# Triangular_Ear_Bass_21.net
KiCad netlist of a schematic drawn in EAGLE
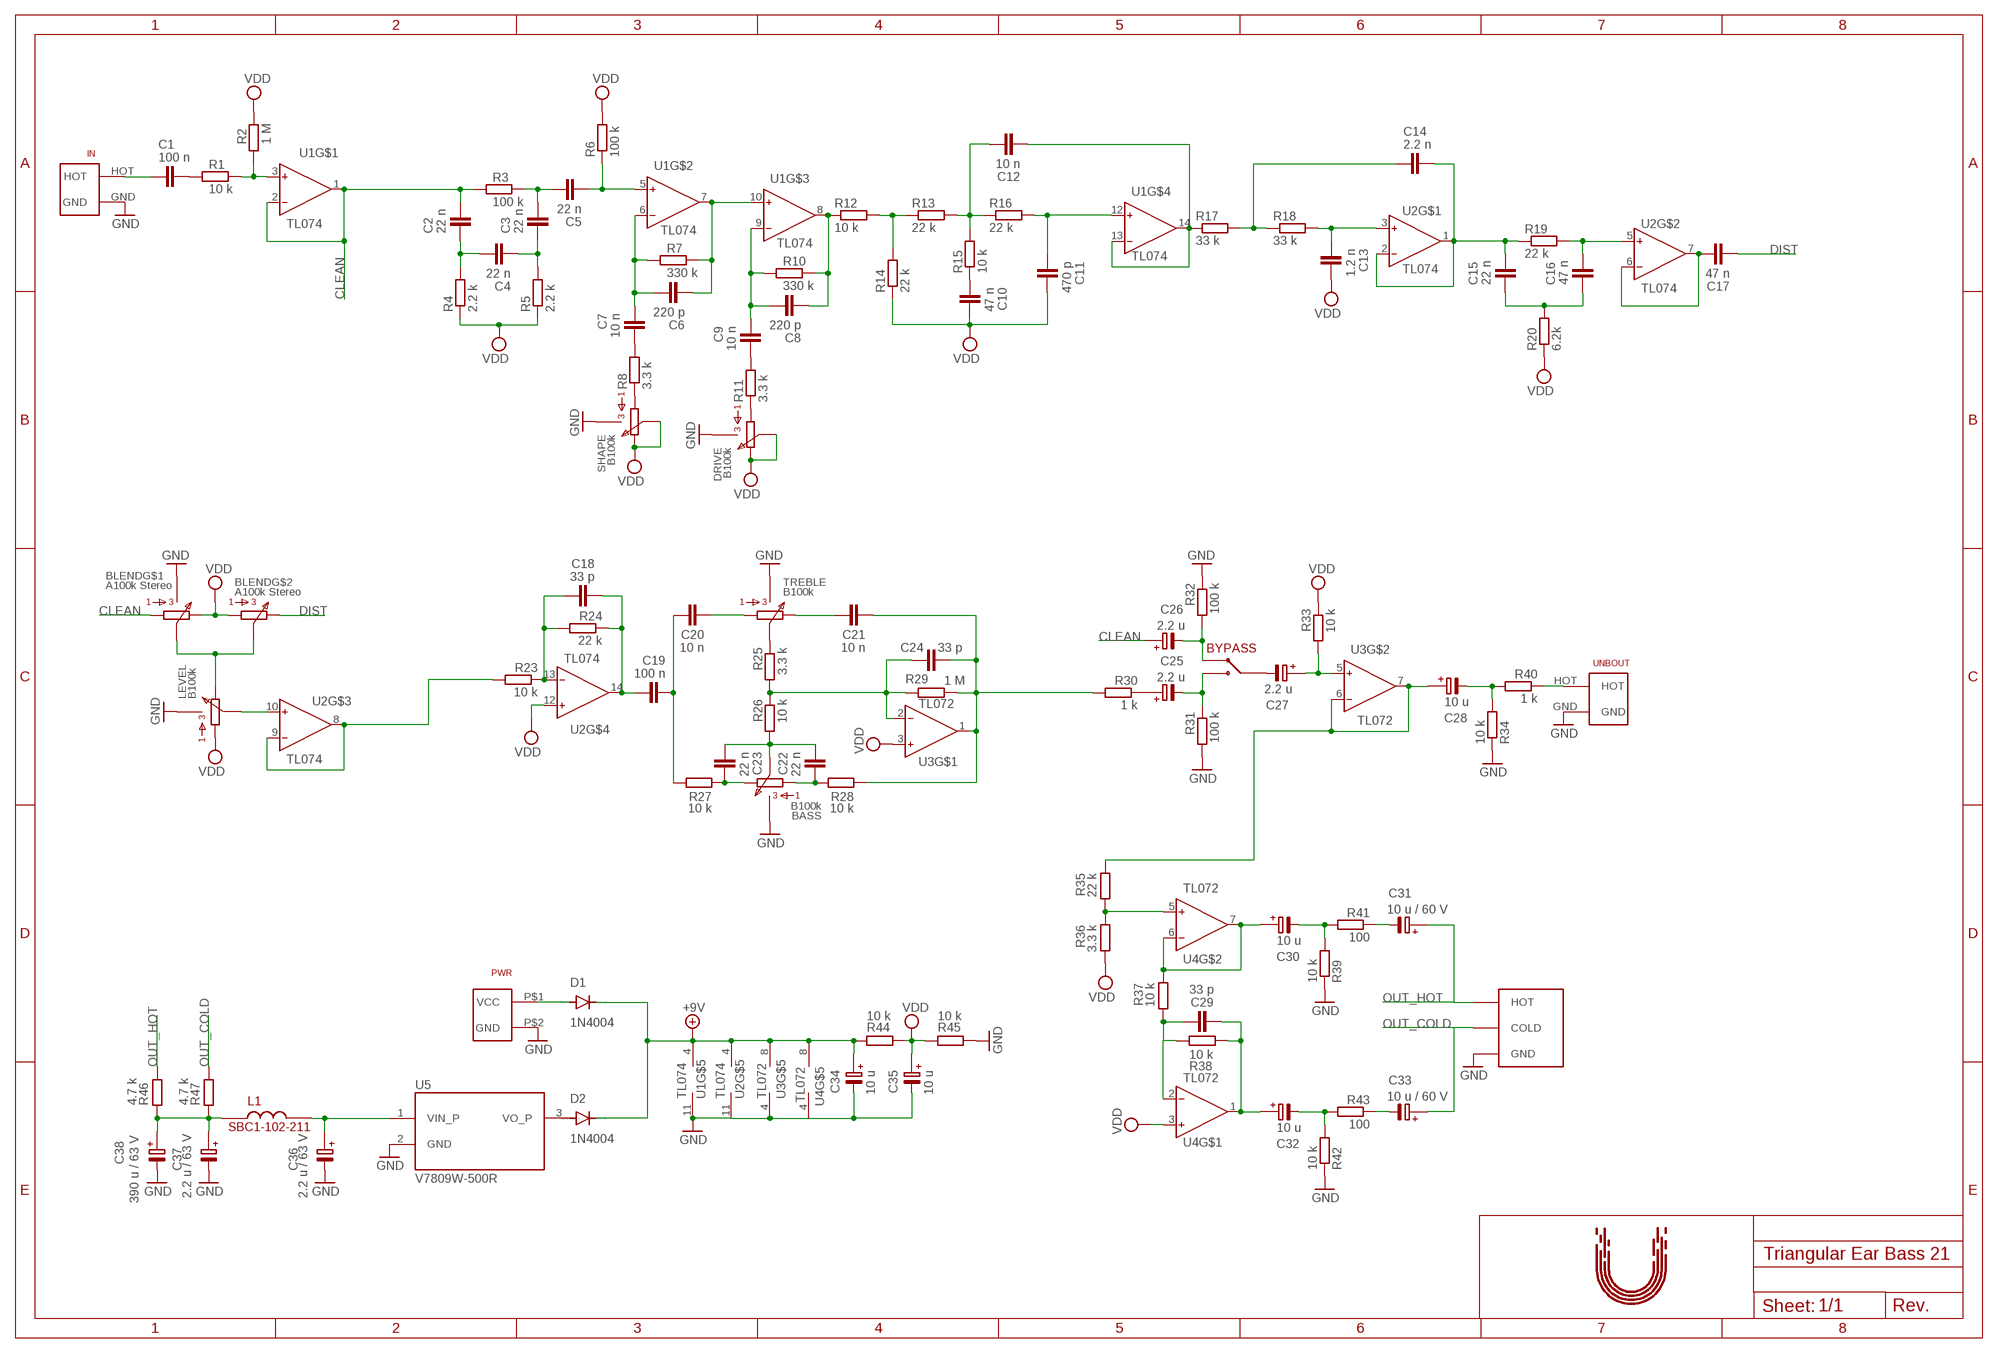
[diagram p0: schematic, sheet 1]

(export (version "E")
  (design (tool "Eeschema 10.0.6"))
  (components
    (comp (ref "BALOUT")
      (value "HOT_COLD")
      (footprint "eagle-import:HOT_COLD")
      (libsource (lib "eagle-import") (part "HOT_COLD"))
    )
    (comp (ref "BASS")
      (value "B100k")
      (footprint "eagle-import:RK09L1140")
      (libsource (lib "eagle-import") (part "RK09L1140"))
    )
    (comp (ref "BLEND")
      (value "A100k Stereo")
      (footprint "eagle-import:RK09L124000Z")
      (libsource (lib "eagle-import") (part "RK09L124000Z"))
    )
    (comp (ref "BYPASS")
      (value "BUTTON")
      (footprint "eagle-import:3-HOLES")
      (libsource (lib "eagle-import") (part "BUTTON"))
    )
    (comp (ref "C1")
      (value "100 n")
      (footprint "eagle-import:C050-035X075")
      (libsource (lib "eagle-import") (part "C-EU050-035X075"))
    )
    (comp (ref "C2")
      (value "22 n")
      (footprint "eagle-import:C050-035X075")
      (libsource (lib "eagle-import") (part "C-EU050-035X075"))
    )
    (comp (ref "C3")
      (value "22 n")
      (footprint "eagle-import:C050-035X075")
      (libsource (lib "eagle-import") (part "C-EU050-035X075"))
    )
    (comp (ref "C4")
      (value "22 n")
      (footprint "eagle-import:C050-035X075")
      (libsource (lib "eagle-import") (part "C-EU050-035X075"))
    )
    (comp (ref "C5")
      (value "22 n")
      (footprint "eagle-import:C050-035X075")
      (libsource (lib "eagle-import") (part "C-EU050-035X075"))
    )
    (comp (ref "C6")
      (value "220 p")
      (footprint "eagle-import:C050-035X075")
      (libsource (lib "eagle-import") (part "C-EU050-035X075"))
    )
    (comp (ref "C7")
      (value "10 n")
      (footprint "eagle-import:C050-035X075")
      (libsource (lib "eagle-import") (part "C-EU050-035X075"))
    )
    (comp (ref "C8")
      (value "220 p")
      (footprint "eagle-import:C050-035X075")
      (libsource (lib "eagle-import") (part "C-EU050-035X075"))
    )
    (comp (ref "C9")
      (value "10 n")
      (footprint "eagle-import:C050-035X075")
      (libsource (lib "eagle-import") (part "C-EU050-035X075"))
    )
    (comp (ref "C10")
      (value "47 n")
      (footprint "eagle-import:C050-035X075")
      (libsource (lib "eagle-import") (part "C-EU050-035X075"))
    )
    (comp (ref "C11")
      (value "470 p")
      (footprint "eagle-import:C050-035X075")
      (libsource (lib "eagle-import") (part "C-EU050-035X075"))
    )
    (comp (ref "C12")
      (value "10 n")
      (footprint "eagle-import:C050-035X075")
      (libsource (lib "eagle-import") (part "C-EU050-035X075"))
    )
    (comp (ref "C13")
      (value "1.2 n")
      (footprint "eagle-import:C050-035X075")
      (libsource (lib "eagle-import") (part "C-EU050-035X075"))
    )
    (comp (ref "C14")
      (value "2.2 n")
      (footprint "eagle-import:C050-035X075")
      (libsource (lib "eagle-import") (part "C-EU050-035X075"))
    )
    (comp (ref "C15")
      (value "22 n")
      (footprint "eagle-import:C050-035X075")
      (libsource (lib "eagle-import") (part "C-EU050-035X075"))
    )
    (comp (ref "C16")
      (value "47 n")
      (footprint "eagle-import:C050-035X075")
      (libsource (lib "eagle-import") (part "C-EU050-035X075"))
    )
    (comp (ref "C17")
      (value "47 n")
      (footprint "eagle-import:C050-035X075")
      (libsource (lib "eagle-import") (part "C-EU050-035X075"))
    )
    (comp (ref "C18")
      (value "33 p")
      (footprint "eagle-import:C050-035X075")
      (libsource (lib "eagle-import") (part "C-EU050-035X075"))
    )
    (comp (ref "C19")
      (value "100 n")
      (footprint "eagle-import:C050-035X075")
      (libsource (lib "eagle-import") (part "C-EU050-035X075"))
    )
    (comp (ref "C20")
      (value "10 n")
      (footprint "eagle-import:C050-035X075")
      (libsource (lib "eagle-import") (part "C-EU050-035X075"))
    )
    (comp (ref "C21")
      (value "10 n")
      (footprint "eagle-import:C050-035X075")
      (libsource (lib "eagle-import") (part "C-EU050-035X075"))
    )
    (comp (ref "C22")
      (value "22 n")
      (footprint "eagle-import:C050-035X075")
      (libsource (lib "eagle-import") (part "C-EU050-035X075"))
    )
    (comp (ref "C23")
      (value "22 n")
      (footprint "eagle-import:C050-035X075")
      (libsource (lib "eagle-import") (part "C-EU050-035X075"))
    )
    (comp (ref "C24")
      (value "33 p")
      (footprint "eagle-import:C050-035X075")
      (libsource (lib "eagle-import") (part "C-EU050-035X075"))
    )
    (comp (ref "C25")
      (value "2.2 u")
      (footprint "eagle-import:E2,0-5")
      (libsource (lib "eagle-import") (part "C-PR-2,0X5"))
    )
    (comp (ref "C26")
      (value "2.2 u")
      (footprint "eagle-import:E2,0-5")
      (libsource (lib "eagle-import") (part "C-PR-2,0X5"))
    )
    (comp (ref "C27")
      (value "2.2 u")
      (footprint "eagle-import:E2,0-5")
      (libsource (lib "eagle-import") (part "C-PR-2,0X5"))
    )
    (comp (ref "C28")
      (value "10 u")
      (footprint "eagle-import:E2,0-5")
      (libsource (lib "eagle-import") (part "C-PR-2,0X5"))
    )
    (comp (ref "C29")
      (value "33 p")
      (footprint "eagle-import:C050-035X075")
      (libsource (lib "eagle-import") (part "C-EU050-035X075"))
    )
    (comp (ref "C30")
      (value "10 u")
      (footprint "eagle-import:E2,0-5")
      (libsource (lib "eagle-import") (part "C-PR-2,0X5"))
    )
    (comp (ref "C31")
      (value "10 u / 60 V")
      (footprint "eagle-import:E2,0-5")
      (libsource (lib "eagle-import") (part "C-PR-2,0X5"))
    )
    (comp (ref "C32")
      (value "10 u")
      (footprint "eagle-import:E2,0-5")
      (libsource (lib "eagle-import") (part "C-PR-2,0X5"))
    )
    (comp (ref "C33")
      (value "10 u / 60 V")
      (footprint "eagle-import:E2,0-5")
      (libsource (lib "eagle-import") (part "C-PR-2,0X5"))
    )
    (comp (ref "C34")
      (value "10 u")
      (footprint "eagle-import:E2,0-5")
      (libsource (lib "eagle-import") (part "C-PR-2,0X5"))
    )
    (comp (ref "C35")
      (value "10 u")
      (footprint "eagle-import:E2,0-5")
      (libsource (lib "eagle-import") (part "C-PR-2,0X5"))
    )
    (comp (ref "C36")
      (value "2.2 u / 63 V")
      (footprint "eagle-import:E2,0-5")
      (libsource (lib "eagle-import") (part "C-PR-2,0X5"))
    )
    (comp (ref "C37")
      (value "2.2 u / 63 V")
      (footprint "eagle-import:E2,0-5")
      (libsource (lib "eagle-import") (part "C-PR-2,0X5"))
    )
    (comp (ref "C38")
      (value "390 u / 63 V")
      (footprint "eagle-import:E5,0-12,5")
      (libsource (lib "eagle-import") (part "C-PR-5,0X12,5"))
    )
    (comp (ref "D1")
      (value "1N4004")
      (footprint "eagle-import:DO41-10")
      (libsource (lib "eagle-import") (part "1N4004"))
    )
    (comp (ref "D2")
      (value "1N4004")
      (footprint "eagle-import:DO41-10")
      (libsource (lib "eagle-import") (part "1N4004"))
    )
    (comp (ref "DRIVE")
      (value "B100k")
      (footprint "eagle-import:RK09L1140")
      (libsource (lib "eagle-import") (part "RK09L1140"))
    )
    (comp (ref "IN")
      (value "UNBALANCED_INPUT_JACK")
      (footprint "eagle-import:BALANCED_INPUT_JACK")
      (libsource (lib "eagle-import") (part "UNBALANCED_INPUT_JACK"))
    )
    (comp (ref "L1")
      (value "SBC1-102-211")
      (footprint "eagle-import:SBC1-102-211")
      (libsource (lib "eagle-import") (part "SBC1-102-211"))
    )
    (comp (ref "LEVEL")
      (value "B100k")
      (footprint "eagle-import:RK09L1140")
      (libsource (lib "eagle-import") (part "RK09L1140"))
    )
    (comp (ref "PWR")
      (value "PWR")
      (footprint "eagle-import:PWR")
      (libsource (lib "eagle-import") (part "PWR"))
    )
    (comp (ref "R1")
      (value "10 k")
      (footprint "eagle-import:0204_7")
      (libsource (lib "eagle-import") (part "R-EU_0204/7"))
    )
    (comp (ref "R2")
      (value "1 M")
      (footprint "eagle-import:0204_7")
      (libsource (lib "eagle-import") (part "R-EU_0204/7"))
    )
    (comp (ref "R3")
      (value "100 k")
      (footprint "eagle-import:0204_7")
      (libsource (lib "eagle-import") (part "R-EU_0204/7"))
    )
    (comp (ref "R4")
      (value "2.2 k")
      (footprint "eagle-import:0204_7")
      (libsource (lib "eagle-import") (part "R-EU_0204/7"))
    )
    (comp (ref "R5")
      (value "2.2 k")
      (footprint "eagle-import:0204_7")
      (libsource (lib "eagle-import") (part "R-EU_0204/7"))
    )
    (comp (ref "R6")
      (value "100 k")
      (footprint "eagle-import:0204_7")
      (libsource (lib "eagle-import") (part "R-EU_0204/7"))
    )
    (comp (ref "R7")
      (value "330 k")
      (footprint "eagle-import:0204_7")
      (libsource (lib "eagle-import") (part "R-EU_0204/7"))
    )
    (comp (ref "R8")
      (value "3.3 k")
      (footprint "eagle-import:0204_7")
      (libsource (lib "eagle-import") (part "R-EU_0204/7"))
    )
    (comp (ref "R10")
      (value "330 k")
      (footprint "eagle-import:0204_7")
      (libsource (lib "eagle-import") (part "R-EU_0204/7"))
    )
    (comp (ref "R11")
      (value "3.3 k")
      (footprint "eagle-import:0204_7")
      (libsource (lib "eagle-import") (part "R-EU_0204/7"))
    )
    (comp (ref "R12")
      (value "10 k")
      (footprint "eagle-import:0204_7")
      (libsource (lib "eagle-import") (part "R-EU_0204/7"))
    )
    (comp (ref "R13")
      (value "22 k")
      (footprint "eagle-import:0204_7")
      (libsource (lib "eagle-import") (part "R-EU_0204/7"))
    )
    (comp (ref "R14")
      (value "22 k")
      (footprint "eagle-import:0204_7")
      (libsource (lib "eagle-import") (part "R-EU_0204/7"))
    )
    (comp (ref "R15")
      (value "10 k")
      (footprint "eagle-import:0204_7")
      (libsource (lib "eagle-import") (part "R-EU_0204/7"))
    )
    (comp (ref "R16")
      (value "22 k")
      (footprint "eagle-import:0204_7")
      (libsource (lib "eagle-import") (part "R-EU_0204/7"))
    )
    (comp (ref "R17")
      (value "33 k")
      (footprint "eagle-import:0204_7")
      (libsource (lib "eagle-import") (part "R-EU_0204/7"))
    )
    (comp (ref "R18")
      (value "33 k")
      (footprint "eagle-import:0204_7")
      (libsource (lib "eagle-import") (part "R-EU_0204/7"))
    )
    (comp (ref "R19")
      (value "22 k")
      (footprint "eagle-import:0204_7")
      (libsource (lib "eagle-import") (part "R-EU_0204/7"))
    )
    (comp (ref "R20")
      (value "6.2k")
      (footprint "eagle-import:0204_7")
      (libsource (lib "eagle-import") (part "R-EU_0204/7"))
    )
    (comp (ref "R23")
      (value "10 k")
      (footprint "eagle-import:0204_7")
      (libsource (lib "eagle-import") (part "R-EU_0204/7"))
    )
    (comp (ref "R24")
      (value "22 k")
      (footprint "eagle-import:0204_7")
      (libsource (lib "eagle-import") (part "R-EU_0204/7"))
    )
    (comp (ref "R25")
      (value "3.3 k")
      (footprint "eagle-import:0204_7")
      (libsource (lib "eagle-import") (part "R-EU_0204/7"))
    )
    (comp (ref "R26")
      (value "10 k")
      (footprint "eagle-import:0204_7")
      (libsource (lib "eagle-import") (part "R-EU_0204/7"))
    )
    (comp (ref "R27")
      (value "10 k")
      (footprint "eagle-import:0204_7")
      (libsource (lib "eagle-import") (part "R-EU_0204/7"))
    )
    (comp (ref "R28")
      (value "10 k")
      (footprint "eagle-import:0204_7")
      (libsource (lib "eagle-import") (part "R-EU_0204/7"))
    )
    (comp (ref "R29")
      (value "1 M")
      (footprint "eagle-import:0204_7")
      (libsource (lib "eagle-import") (part "R-EU_0204/7"))
    )
    (comp (ref "R30")
      (value "1 k")
      (footprint "eagle-import:0204_7")
      (libsource (lib "eagle-import") (part "R-EU_0204/7"))
    )
    (comp (ref "R31")
      (value "100 k")
      (footprint "eagle-import:0204_7")
      (libsource (lib "eagle-import") (part "R-EU_0204/7"))
    )
    (comp (ref "R32")
      (value "100 k")
      (footprint "eagle-import:0204_7")
      (libsource (lib "eagle-import") (part "R-EU_0204/7"))
    )
    (comp (ref "R33")
      (value "10 k")
      (footprint "eagle-import:0204_7")
      (libsource (lib "eagle-import") (part "R-EU_0204/7"))
    )
    (comp (ref "R34")
      (value "10 k")
      (footprint "eagle-import:0204_7")
      (libsource (lib "eagle-import") (part "R-EU_0204/7"))
    )
    (comp (ref "R35")
      (value "22 k")
      (footprint "eagle-import:0204_7")
      (libsource (lib "eagle-import") (part "R-EU_0204/7"))
    )
    (comp (ref "R36")
      (value "3.3 k")
      (footprint "eagle-import:0204_7")
      (libsource (lib "eagle-import") (part "R-EU_0204/7"))
    )
    (comp (ref "R37")
      (value "10 k")
      (footprint "eagle-import:0204_7")
      (libsource (lib "eagle-import") (part "R-EU_0204/7"))
    )
    (comp (ref "R38")
      (value "10 k")
      (footprint "eagle-import:0204_7")
      (libsource (lib "eagle-import") (part "R-EU_0204/7"))
    )
    (comp (ref "R39")
      (value "10 k")
      (footprint "eagle-import:0204_7")
      (libsource (lib "eagle-import") (part "R-EU_0204/7"))
    )
    (comp (ref "R40")
      (value "1 k")
      (footprint "eagle-import:0204_7")
      (libsource (lib "eagle-import") (part "R-EU_0204/7"))
    )
    (comp (ref "R41")
      (value "100")
      (footprint "eagle-import:0204_7")
      (libsource (lib "eagle-import") (part "R-EU_0204/7"))
    )
    (comp (ref "R42")
      (value "10 k")
      (footprint "eagle-import:0204_7")
      (libsource (lib "eagle-import") (part "R-EU_0204/7"))
    )
    (comp (ref "R43")
      (value "100")
      (footprint "eagle-import:0204_7")
      (libsource (lib "eagle-import") (part "R-EU_0204/7"))
    )
    (comp (ref "R44")
      (value "10 k")
      (footprint "eagle-import:0204_7")
      (libsource (lib "eagle-import") (part "R-EU_0204/7"))
    )
    (comp (ref "R45")
      (value "10 k")
      (footprint "eagle-import:0204_7")
      (libsource (lib "eagle-import") (part "R-EU_0204/7"))
    )
    (comp (ref "R46")
      (value "4.7 k")
      (footprint "eagle-import:0204_7")
      (libsource (lib "eagle-import") (part "R-EU_0204/7"))
    )
    (comp (ref "R47")
      (value "4.7 k")
      (footprint "eagle-import:0204_7")
      (libsource (lib "eagle-import") (part "R-EU_0204/7"))
    )
    (comp (ref "SHAPE")
      (value "B100k")
      (footprint "eagle-import:RK09L1140")
      (libsource (lib "eagle-import") (part "RK09L1140"))
    )
    (comp (ref "TREBLE")
      (value "B100k")
      (footprint "eagle-import:RK09L1140")
      (libsource (lib "eagle-import") (part "RK09L1140"))
    )
    (comp (ref "U$1")
      (value "UTBULT_DESIGN4")
      (footprint "eagle-import:UD_4")
      (libsource (lib "eagle-import") (part "UTBULT_DESIGN4"))
    )
    (comp (ref "U1")
      (value "TL074")
      (footprint "eagle-import:DIP762W53P254L1969H508Q14B")
      (fields (field (name "MPN") "TL074CN"))
      (libsource (lib "eagle-import") (part "TL074IDTPDIP-14"))
    )
    (comp (ref "U2")
      (value "TL074")
      (footprint "eagle-import:DIP762W53P254L1969H508Q14B")
      (fields (field (name "MPN") "TL074CN"))
      (libsource (lib "eagle-import") (part "TL074IDTPDIP-14"))
    )
    (comp (ref "U3")
      (value "TL072")
      (footprint "eagle-import:DIP762W53P254L980H508Q8B")
      (fields (field (name "MPN") "TL072IP"))
      (libsource (lib "eagle-import") (part "TL072PDIP-8"))
    )
    (comp (ref "U4")
      (value "TL072")
      (footprint "eagle-import:DIP762W53P254L980H508Q8B")
      (fields (field (name "MPN") "TL072IP"))
      (libsource (lib "eagle-import") (part "TL072PDIP-8"))
    )
    (comp (ref "U5")
      (value "V7809W-500R")
      (footprint "eagle-import:CONV_V7809W-500R")
      (libsource (lib "eagle-import") (part "V7809W-500R"))
    )
    (comp (ref "UNBOUT")
      (value "UNBALANCED_INPUT_JACK")
      (footprint "eagle-import:BALANCED_INPUT_JACK")
      (libsource (lib "eagle-import") (part "UNBALANCED_INPUT_JACK"))
    )
  )
  (nets
    (net (code "1") (name "+9V") (class "Default")
      (node (ref "C34") (pin "+") (pinfunction "+_+") (pintype "passive"))
      (node (ref "D1") (pin "C") (pinfunction "C_C") (pintype "passive"))
      (node (ref "D2") (pin "C") (pinfunction "C_C") (pintype "passive"))
      (node (ref "R44") (pin "1") (pinfunction "1_1") (pintype "passive"))
      (node (ref "U1") (pin "4") (pinfunction "V+_4") (pintype "power_in"))
      (node (ref "U2") (pin "4") (pinfunction "V+_4") (pintype "power_in"))
      (node (ref "U3") (pin "8") (pinfunction "V+_8") (pintype "power_in"))
      (node (ref "U4") (pin "8") (pinfunction "V+_8") (pintype "power_in"))
    )
    (net (code "2") (name "/CLEAN") (class "Default")
      (node (ref "BLEND") (pin "P$1") (pinfunction "1_P$1") (pintype "passive"))
      (node (ref "C2") (pin "2") (pinfunction "2_2") (pintype "passive"))
      (node (ref "C26") (pin "+") (pinfunction "+_+") (pintype "passive"))
      (node (ref "R3") (pin "1") (pinfunction "1_1") (pintype "passive"))
      (node (ref "U1") (pin "1") (pinfunction "OUT_1") (pintype "output"))
      (node (ref "U1") (pin "2") (pinfunction "IN-_2") (pintype "input"))
    )
    (net (code "3") (name "/DIST") (class "Default")
      (node (ref "BLEND") (pin "P$8") (pinfunction "3_P$8") (pintype "passive"))
      (node (ref "C17") (pin "1") (pinfunction "1_1") (pintype "passive"))
    )
    (net (code "4") (name "/OUT_COLD") (class "Default")
      (node (ref "BALOUT") (pin "P$3") (pinfunction "COLD_P$3") (pintype "bidirectional"))
      (node (ref "C33") (pin "+") (pinfunction "+_+") (pintype "passive"))
      (node (ref "R47") (pin "2") (pinfunction "2_2") (pintype "passive"))
    )
    (net (code "5") (name "/OUT_HOT") (class "Default")
      (node (ref "BALOUT") (pin "P$2") (pinfunction "HOT_P$2") (pintype "bidirectional"))
      (node (ref "C31") (pin "+") (pinfunction "+_+") (pintype "passive"))
      (node (ref "R46") (pin "2") (pinfunction "2_2") (pintype "passive"))
    )
    (net (code "6") (name "GND") (class "Default")
      (node (ref "BALOUT") (pin "P$1") (pinfunction "GND_P$1") (pintype "bidirectional"))
      (node (ref "BASS") (pin "P$4") (pinfunction "P$1_P$4") (pintype "bidirectional"))
      (node (ref "BASS") (pin "P$5") (pinfunction "P$1_P$5") (pintype "bidirectional"))
      (node (ref "BLEND") (pin "P$4") (pinfunction "P$1_P$4") (pintype "bidirectional"))
      (node (ref "BLEND") (pin "P$5") (pinfunction "P$1_P$5") (pintype "bidirectional"))
      (node (ref "C34") (pin "-") (pinfunction "-_-") (pintype "passive"))
      (node (ref "C35") (pin "-") (pinfunction "-_-") (pintype "passive"))
      (node (ref "C36") (pin "-") (pinfunction "-_-") (pintype "passive"))
      (node (ref "C37") (pin "-") (pinfunction "-_-") (pintype "passive"))
      (node (ref "C38") (pin "-") (pinfunction "-_-") (pintype "passive"))
      (node (ref "DRIVE") (pin "P$4") (pinfunction "P$1_P$4") (pintype "bidirectional"))
      (node (ref "DRIVE") (pin "P$5") (pinfunction "P$1_P$5") (pintype "bidirectional"))
      (node (ref "IN") (pin "GND") (pinfunction "GND_GND") (pintype "bidirectional"))
      (node (ref "LEVEL") (pin "P$4") (pinfunction "P$1_P$4") (pintype "bidirectional"))
      (node (ref "LEVEL") (pin "P$5") (pinfunction "P$1_P$5") (pintype "bidirectional"))
      (node (ref "PWR") (pin "P$2") (pinfunction "GND_P$2") (pintype "bidirectional"))
      (node (ref "R31") (pin "2") (pinfunction "2_2") (pintype "passive"))
      (node (ref "R32") (pin "1") (pinfunction "1_1") (pintype "passive"))
      (node (ref "R34") (pin "1") (pinfunction "1_1") (pintype "passive"))
      (node (ref "R39") (pin "1") (pinfunction "1_1") (pintype "passive"))
      (node (ref "R42") (pin "1") (pinfunction "1_1") (pintype "passive"))
      (node (ref "R45") (pin "2") (pinfunction "2_2") (pintype "passive"))
      (node (ref "SHAPE") (pin "P$4") (pinfunction "P$1_P$4") (pintype "bidirectional"))
      (node (ref "SHAPE") (pin "P$5") (pinfunction "P$1_P$5") (pintype "bidirectional"))
      (node (ref "TREBLE") (pin "P$4") (pinfunction "P$1_P$4") (pintype "bidirectional"))
      (node (ref "TREBLE") (pin "P$5") (pinfunction "P$1_P$5") (pintype "bidirectional"))
      (node (ref "U1") (pin "11") (pinfunction "V-_11") (pintype "power_in"))
      (node (ref "U2") (pin "11") (pinfunction "V-_11") (pintype "power_in"))
      (node (ref "U3") (pin "4") (pinfunction "V-_4") (pintype "power_in"))
      (node (ref "U4") (pin "4") (pinfunction "V-_4") (pintype "power_in"))
      (node (ref "U5") (pin "2") (pinfunction "GND_2") (pintype "power_in"))
      (node (ref "UNBOUT") (pin "GND") (pinfunction "GND_GND") (pintype "bidirectional"))
    )
    (net (code "7") (name "Net-(BASS-1)") (class "Default")
      (node (ref "BASS") (pin "P$1") (pinfunction "1_P$1") (pintype "passive"))
      (node (ref "C22") (pin "2") (pinfunction "2_2") (pintype "passive"))
      (node (ref "R28") (pin "2") (pinfunction "2_2") (pintype "passive"))
    )
    (net (code "8") (name "Net-(BASS-2)") (class "Default")
      (node (ref "BASS") (pin "P$2") (pinfunction "2_P$2") (pintype "passive"))
      (node (ref "C22") (pin "1") (pinfunction "1_1") (pintype "passive"))
      (node (ref "C23") (pin "1") (pinfunction "1_1") (pintype "passive"))
      (node (ref "R26") (pin "2") (pinfunction "2_2") (pintype "passive"))
    )
    (net (code "9") (name "Net-(BASS-3)") (class "Default")
      (node (ref "BASS") (pin "P$3") (pinfunction "3_P$3") (pintype "passive"))
      (node (ref "C23") (pin "2") (pinfunction "2_2") (pintype "passive"))
      (node (ref "R27") (pin "1") (pinfunction "1_1") (pintype "passive"))
    )
    (net (code "10") (name "Net-(BLENDA-2)") (class "Default")
      (node (ref "BLEND") (pin "P$2") (pinfunction "2_P$2") (pintype "passive"))
      (node (ref "BLEND") (pin "P$7") (pinfunction "2_P$7") (pintype "passive"))
      (node (ref "LEVEL") (pin "P$3") (pinfunction "3_P$3") (pintype "passive"))
    )
    (net (code "11") (name "Net-(BYPASS-PadP$1)") (class "Default")
      (node (ref "BYPASS") (pin "P$1") (pinfunction "P$1_P$1") (pintype "bidirectional"))
      (node (ref "C26") (pin "-") (pinfunction "-_-") (pintype "passive"))
      (node (ref "R32") (pin "2") (pinfunction "2_2") (pintype "passive"))
    )
    (net (code "12") (name "Net-(BYPASS-PadP$2)") (class "Default")
      (node (ref "BYPASS") (pin "P$2") (pinfunction "P$2_P$2") (pintype "bidirectional"))
      (node (ref "C27") (pin "-") (pinfunction "-_-") (pintype "passive"))
    )
    (net (code "13") (name "Net-(BYPASS-PadP$3)") (class "Default")
      (node (ref "BYPASS") (pin "P$3") (pinfunction "P$3_P$3") (pintype "bidirectional"))
      (node (ref "C25") (pin "-") (pinfunction "-_-") (pintype "passive"))
      (node (ref "R31") (pin "1") (pinfunction "1_1") (pintype "passive"))
    )
    (net (code "14") (name "Net-(C1-Pad1)") (class "Default")
      (node (ref "C1") (pin "1") (pinfunction "1_1") (pintype "passive"))
      (node (ref "IN") (pin "HOT") (pinfunction "HOT_HOT") (pintype "bidirectional"))
    )
    (net (code "15") (name "Net-(C1-Pad2)") (class "Default")
      (node (ref "C1") (pin "2") (pinfunction "2_2") (pintype "passive"))
      (node (ref "R1") (pin "1") (pinfunction "1_1") (pintype "passive"))
    )
    (net (code "16") (name "Net-(C2-Pad1)") (class "Default")
      (node (ref "C2") (pin "1") (pinfunction "1_1") (pintype "passive"))
      (node (ref "C4") (pin "2") (pinfunction "2_2") (pintype "passive"))
      (node (ref "R4") (pin "2") (pinfunction "2_2") (pintype "passive"))
    )
    (net (code "17") (name "Net-(C3-Pad1)") (class "Default")
      (node (ref "C3") (pin "1") (pinfunction "1_1") (pintype "passive"))
      (node (ref "C4") (pin "1") (pinfunction "1_1") (pintype "passive"))
      (node (ref "R5") (pin "2") (pinfunction "2_2") (pintype "passive"))
    )
    (net (code "18") (name "Net-(C3-Pad2)") (class "Default")
      (node (ref "C3") (pin "2") (pinfunction "2_2") (pintype "passive"))
      (node (ref "C5") (pin "2") (pinfunction "2_2") (pintype "passive"))
      (node (ref "R3") (pin "2") (pinfunction "2_2") (pintype "passive"))
    )
    (net (code "19") (name "Net-(C7-Pad2)") (class "Default")
      (node (ref "C7") (pin "2") (pinfunction "2_2") (pintype "passive"))
      (node (ref "R8") (pin "2") (pinfunction "2_2") (pintype "passive"))
    )
    (net (code "20") (name "Net-(C9-Pad2)") (class "Default")
      (node (ref "C9") (pin "2") (pinfunction "2_2") (pintype "passive"))
      (node (ref "R11") (pin "2") (pinfunction "2_2") (pintype "passive"))
    )
    (net (code "21") (name "Net-(C10-Pad1)") (class "Default")
      (node (ref "C10") (pin "1") (pinfunction "1_1") (pintype "passive"))
      (node (ref "R15") (pin "1") (pinfunction "1_1") (pintype "passive"))
    )
    (net (code "22") (name "Net-(C12-Pad2)") (class "Default")
      (node (ref "C12") (pin "2") (pinfunction "2_2") (pintype "passive"))
      (node (ref "R13") (pin "2") (pinfunction "2_2") (pintype "passive"))
      (node (ref "R15") (pin "2") (pinfunction "2_2") (pintype "passive"))
      (node (ref "R16") (pin "1") (pinfunction "1_1") (pintype "passive"))
    )
    (net (code "23") (name "Net-(C14-Pad1)") (class "Default")
      (node (ref "C14") (pin "1") (pinfunction "1_1") (pintype "passive"))
      (node (ref "R17") (pin "2") (pinfunction "2_2") (pintype "passive"))
      (node (ref "R18") (pin "1") (pinfunction "1_1") (pintype "passive"))
    )
    (net (code "24") (name "Net-(C15-Pad1)") (class "Default")
      (node (ref "C15") (pin "1") (pinfunction "1_1") (pintype "passive"))
      (node (ref "C16") (pin "1") (pinfunction "1_1") (pintype "passive"))
      (node (ref "R20") (pin "2") (pinfunction "2_2") (pintype "passive"))
    )
    (net (code "25") (name "Net-(C19-Pad1)") (class "Default")
      (node (ref "C19") (pin "1") (pinfunction "1_1") (pintype "passive"))
      (node (ref "C20") (pin "2") (pinfunction "2_2") (pintype "passive"))
      (node (ref "R27") (pin "2") (pinfunction "2_2") (pintype "passive"))
    )
    (net (code "26") (name "Net-(C25-Pad+)") (class "Default")
      (node (ref "C25") (pin "+") (pinfunction "+_+") (pintype "passive"))
      (node (ref "R30") (pin "1") (pinfunction "1_1") (pintype "passive"))
    )
    (net (code "27") (name "Net-(C28-Pad-)") (class "Default")
      (node (ref "C28") (pin "-") (pinfunction "-_-") (pintype "passive"))
      (node (ref "R34") (pin "2") (pinfunction "2_2") (pintype "passive"))
      (node (ref "R40") (pin "2") (pinfunction "2_2") (pintype "passive"))
    )
    (net (code "28") (name "Net-(C30-Pad-)") (class "Default")
      (node (ref "C30") (pin "-") (pinfunction "-_-") (pintype "passive"))
      (node (ref "R39") (pin "2") (pinfunction "2_2") (pintype "passive"))
      (node (ref "R41") (pin "2") (pinfunction "2_2") (pintype "passive"))
    )
    (net (code "29") (name "Net-(C31-Pad-)") (class "Default")
      (node (ref "C31") (pin "-") (pinfunction "-_-") (pintype "passive"))
      (node (ref "R41") (pin "1") (pinfunction "1_1") (pintype "passive"))
    )
    (net (code "30") (name "Net-(C32-Pad-)") (class "Default")
      (node (ref "C32") (pin "-") (pinfunction "-_-") (pintype "passive"))
      (node (ref "R42") (pin "2") (pinfunction "2_2") (pintype "passive"))
      (node (ref "R43") (pin "2") (pinfunction "2_2") (pintype "passive"))
    )
    (net (code "31") (name "Net-(C33-Pad-)") (class "Default")
      (node (ref "C33") (pin "-") (pinfunction "-_-") (pintype "passive"))
      (node (ref "R43") (pin "1") (pinfunction "1_1") (pintype "passive"))
    )
    (net (code "32") (name "Net-(C37-Pad+)") (class "Default")
      (node (ref "C37") (pin "+") (pinfunction "+_+") (pintype "passive"))
      (node (ref "C38") (pin "+") (pinfunction "+_+") (pintype "passive"))
      (node (ref "L1") (pin "P$1") (pinfunction "P$1_P$1") (pintype "bidirectional"))
      (node (ref "R46") (pin "1") (pinfunction "1_1") (pintype "passive"))
      (node (ref "R47") (pin "1") (pinfunction "1_1") (pintype "passive"))
    )
    (net (code "33") (name "Net-(DRIVE-1)") (class "Default")
      (node (ref "DRIVE") (pin "P$1") (pinfunction "1_P$1") (pintype "passive"))
      (node (ref "R11") (pin "1") (pinfunction "1_1") (pintype "passive"))
    )
    (net (code "34") (name "Net-(LEVEL-2)") (class "Default")
      (node (ref "LEVEL") (pin "P$2") (pinfunction "2_P$2") (pintype "passive"))
      (node (ref "U2") (pin "10") (pinfunction "IN+_10") (pintype "input"))
    )
    (net (code "35") (name "Net-(PWR-VCC)") (class "Default")
      (node (ref "D1") (pin "A") (pinfunction "A_A") (pintype "passive"))
      (node (ref "PWR") (pin "P$1") (pinfunction "VCC_P$1") (pintype "bidirectional"))
    )
    (net (code "36") (name "Net-(R12-Pad2)") (class "Default")
      (node (ref "R12") (pin "2") (pinfunction "2_2") (pintype "passive"))
      (node (ref "R13") (pin "1") (pinfunction "1_1") (pintype "passive"))
      (node (ref "R14") (pin "2") (pinfunction "2_2") (pintype "passive"))
    )
    (net (code "37") (name "Net-(R40-Pad1)") (class "Default")
      (node (ref "R40") (pin "1") (pinfunction "1_1") (pintype "passive"))
      (node (ref "UNBOUT") (pin "HOT") (pinfunction "HOT_HOT") (pintype "bidirectional"))
    )
    (net (code "38") (name "Net-(SHAPE-1)") (class "Default")
      (node (ref "R8") (pin "1") (pinfunction "1_1") (pintype "passive"))
      (node (ref "SHAPE") (pin "P$1") (pinfunction "1_P$1") (pintype "passive"))
    )
    (net (code "39") (name "Net-(TREBLE-1)") (class "Default")
      (node (ref "C20") (pin "1") (pinfunction "1_1") (pintype "passive"))
      (node (ref "TREBLE") (pin "P$1") (pinfunction "1_P$1") (pintype "passive"))
    )
    (net (code "40") (name "Net-(TREBLE-2)") (class "Default")
      (node (ref "R25") (pin "1") (pinfunction "1_1") (pintype "passive"))
      (node (ref "TREBLE") (pin "P$2") (pinfunction "2_P$2") (pintype "passive"))
    )
    (net (code "41") (name "Net-(TREBLE-3)") (class "Default")
      (node (ref "C21") (pin "2") (pinfunction "2_2") (pintype "passive"))
      (node (ref "TREBLE") (pin "P$3") (pinfunction "3_P$3") (pintype "passive"))
    )
    (net (code "42") (name "Net-(U1A-IN+)") (class "Default")
      (node (ref "R1") (pin "2") (pinfunction "2_2") (pintype "passive"))
      (node (ref "R2") (pin "1") (pinfunction "1_1") (pintype "passive"))
      (node (ref "U1") (pin "3") (pinfunction "IN+_3") (pintype "input"))
    )
    (net (code "43") (name "Net-(U1B-IN+)") (class "Default")
      (node (ref "C5") (pin "1") (pinfunction "1_1") (pintype "passive"))
      (node (ref "R6") (pin "1") (pinfunction "1_1") (pintype "passive"))
      (node (ref "U1") (pin "5") (pinfunction "IN+_5") (pintype "input"))
    )
    (net (code "44") (name "Net-(U1B-IN-)") (class "Default")
      (node (ref "C6") (pin "2") (pinfunction "2_2") (pintype "passive"))
      (node (ref "C7") (pin "1") (pinfunction "1_1") (pintype "passive"))
      (node (ref "R7") (pin "1") (pinfunction "1_1") (pintype "passive"))
      (node (ref "U1") (pin "6") (pinfunction "IN-_6") (pintype "input"))
    )
    (net (code "45") (name "Net-(U1B-OUT)") (class "Default")
      (node (ref "C6") (pin "1") (pinfunction "1_1") (pintype "passive"))
      (node (ref "R7") (pin "2") (pinfunction "2_2") (pintype "passive"))
      (node (ref "U1") (pin "10") (pinfunction "IN+_10") (pintype "input"))
      (node (ref "U1") (pin "7") (pinfunction "OUT_7") (pintype "output"))
    )
    (net (code "46") (name "Net-(U1C-IN-)") (class "Default")
      (node (ref "C8") (pin "2") (pinfunction "2_2") (pintype "passive"))
      (node (ref "C9") (pin "1") (pinfunction "1_1") (pintype "passive"))
      (node (ref "R10") (pin "1") (pinfunction "1_1") (pintype "passive"))
      (node (ref "U1") (pin "9") (pinfunction "IN-_9") (pintype "input"))
    )
    (net (code "47") (name "Net-(U1C-OUT)") (class "Default")
      (node (ref "C8") (pin "1") (pinfunction "1_1") (pintype "passive"))
      (node (ref "R10") (pin "2") (pinfunction "2_2") (pintype "passive"))
      (node (ref "R12") (pin "1") (pinfunction "1_1") (pintype "passive"))
      (node (ref "U1") (pin "8") (pinfunction "OUT_8") (pintype "output"))
    )
    (net (code "48") (name "Net-(U1D-IN+)") (class "Default")
      (node (ref "C11") (pin "1") (pinfunction "1_1") (pintype "passive"))
      (node (ref "R16") (pin "2") (pinfunction "2_2") (pintype "passive"))
      (node (ref "U1") (pin "12") (pinfunction "IN+_12") (pintype "input"))
    )
    (net (code "49") (name "Net-(U1D-IN-)") (class "Default")
      (node (ref "C12") (pin "1") (pinfunction "1_1") (pintype "passive"))
      (node (ref "R17") (pin "1") (pinfunction "1_1") (pintype "passive"))
      (node (ref "U1") (pin "13") (pinfunction "IN-_13") (pintype "input"))
      (node (ref "U1") (pin "14") (pinfunction "OUT_14") (pintype "output"))
    )
    (net (code "50") (name "Net-(U2A-IN+)") (class "Default")
      (node (ref "C13") (pin "1") (pinfunction "1_1") (pintype "passive"))
      (node (ref "R18") (pin "2") (pinfunction "2_2") (pintype "passive"))
      (node (ref "U2") (pin "3") (pinfunction "IN+_3") (pintype "input"))
    )
    (net (code "51") (name "Net-(U2A-IN-)") (class "Default")
      (node (ref "C14") (pin "2") (pinfunction "2_2") (pintype "passive"))
      (node (ref "C15") (pin "2") (pinfunction "2_2") (pintype "passive"))
      (node (ref "R19") (pin "1") (pinfunction "1_1") (pintype "passive"))
      (node (ref "U2") (pin "1") (pinfunction "OUT_1") (pintype "output"))
      (node (ref "U2") (pin "2") (pinfunction "IN-_2") (pintype "input"))
    )
    (net (code "52") (name "Net-(U2B-IN+)") (class "Default")
      (node (ref "C16") (pin "2") (pinfunction "2_2") (pintype "passive"))
      (node (ref "R19") (pin "2") (pinfunction "2_2") (pintype "passive"))
      (node (ref "U2") (pin "5") (pinfunction "IN+_5") (pintype "input"))
    )
    (net (code "53") (name "Net-(U2B-IN-)") (class "Default")
      (node (ref "C17") (pin "2") (pinfunction "2_2") (pintype "passive"))
      (node (ref "U2") (pin "6") (pinfunction "IN-_6") (pintype "input"))
      (node (ref "U2") (pin "7") (pinfunction "OUT_7") (pintype "output"))
    )
    (net (code "54") (name "Net-(U2C-IN-)") (class "Default")
      (node (ref "R23") (pin "2") (pinfunction "2_2") (pintype "passive"))
      (node (ref "U2") (pin "8") (pinfunction "OUT_8") (pintype "output"))
      (node (ref "U2") (pin "9") (pinfunction "IN-_9") (pintype "input"))
    )
    (net (code "55") (name "Net-(U2D-IN-)") (class "Default")
      (node (ref "C18") (pin "2") (pinfunction "2_2") (pintype "passive"))
      (node (ref "R23") (pin "1") (pinfunction "1_1") (pintype "passive"))
      (node (ref "R24") (pin "2") (pinfunction "2_2") (pintype "passive"))
      (node (ref "U2") (pin "13") (pinfunction "IN-_13") (pintype "input"))
    )
    (net (code "56") (name "Net-(U2D-OUT)") (class "Default")
      (node (ref "C18") (pin "1") (pinfunction "1_1") (pintype "passive"))
      (node (ref "C19") (pin "2") (pinfunction "2_2") (pintype "passive"))
      (node (ref "R24") (pin "1") (pinfunction "1_1") (pintype "passive"))
      (node (ref "U2") (pin "14") (pinfunction "OUT_14") (pintype "output"))
    )
    (net (code "57") (name "Net-(U3A-IN-)") (class "Default")
      (node (ref "C24") (pin "2") (pinfunction "2_2") (pintype "passive"))
      (node (ref "R25") (pin "2") (pinfunction "2_2") (pintype "passive"))
      (node (ref "R26") (pin "1") (pinfunction "1_1") (pintype "passive"))
      (node (ref "R29") (pin "1") (pinfunction "1_1") (pintype "passive"))
      (node (ref "U3") (pin "2") (pinfunction "IN-_2") (pintype "input"))
    )
    (net (code "58") (name "Net-(U3A-OUT)") (class "Default")
      (node (ref "C21") (pin "1") (pinfunction "1_1") (pintype "passive"))
      (node (ref "C24") (pin "1") (pinfunction "1_1") (pintype "passive"))
      (node (ref "R28") (pin "1") (pinfunction "1_1") (pintype "passive"))
      (node (ref "R29") (pin "2") (pinfunction "2_2") (pintype "passive"))
      (node (ref "R30") (pin "2") (pinfunction "2_2") (pintype "passive"))
      (node (ref "U3") (pin "1") (pinfunction "OUT_1") (pintype "output"))
    )
    (net (code "59") (name "Net-(U3B-IN+)") (class "Default")
      (node (ref "C27") (pin "+") (pinfunction "+_+") (pintype "passive"))
      (node (ref "R33") (pin "2") (pinfunction "2_2") (pintype "passive"))
      (node (ref "U3") (pin "5") (pinfunction "IN+_5") (pintype "input"))
    )
    (net (code "60") (name "Net-(U3B-IN-)") (class "Default")
      (node (ref "C28") (pin "+") (pinfunction "+_+") (pintype "passive"))
      (node (ref "R35") (pin "1") (pinfunction "1_1") (pintype "passive"))
      (node (ref "U3") (pin "6") (pinfunction "IN-_6") (pintype "input"))
      (node (ref "U3") (pin "7") (pinfunction "OUT_7") (pintype "output"))
    )
    (net (code "61") (name "Net-(U4A-IN-)") (class "Default")
      (node (ref "C29") (pin "2") (pinfunction "2_2") (pintype "passive"))
      (node (ref "R37") (pin "2") (pinfunction "2_2") (pintype "passive"))
      (node (ref "R38") (pin "1") (pinfunction "1_1") (pintype "passive"))
      (node (ref "U4") (pin "2") (pinfunction "IN-_2") (pintype "input"))
    )
    (net (code "62") (name "Net-(U4A-OUT)") (class "Default")
      (node (ref "C29") (pin "1") (pinfunction "1_1") (pintype "passive"))
      (node (ref "C32") (pin "+") (pinfunction "+_+") (pintype "passive"))
      (node (ref "R38") (pin "2") (pinfunction "2_2") (pintype "passive"))
      (node (ref "U4") (pin "1") (pinfunction "OUT_1") (pintype "output"))
    )
    (net (code "63") (name "Net-(U4B-IN+)") (class "Default")
      (node (ref "R35") (pin "2") (pinfunction "2_2") (pintype "passive"))
      (node (ref "R36") (pin "1") (pinfunction "1_1") (pintype "passive"))
      (node (ref "U4") (pin "5") (pinfunction "IN+_5") (pintype "input"))
    )
    (net (code "64") (name "Net-(U4B-IN-)") (class "Default")
      (node (ref "C30") (pin "+") (pinfunction "+_+") (pintype "passive"))
      (node (ref "R37") (pin "1") (pinfunction "1_1") (pintype "passive"))
      (node (ref "U4") (pin "6") (pinfunction "IN-_6") (pintype "input"))
      (node (ref "U4") (pin "7") (pinfunction "OUT_7") (pintype "output"))
    )
    (net (code "65") (name "Net-(U5-VIN_P)") (class "Default")
      (node (ref "C36") (pin "+") (pinfunction "+_+") (pintype "passive"))
      (node (ref "L1") (pin "P$2") (pinfunction "P$2_P$2") (pintype "bidirectional"))
      (node (ref "U5") (pin "1") (pinfunction "VIN_P_1") (pintype "input"))
    )
    (net (code "66") (name "Net-(U5-VO_P)") (class "Default")
      (node (ref "D2") (pin "A") (pinfunction "A_A") (pintype "passive"))
      (node (ref "U5") (pin "3") (pinfunction "VO_P_3") (pintype "output"))
    )
    (net (code "67") (name "VDD") (class "Default")
      (node (ref "BLEND") (pin "P$3") (pinfunction "3_P$3") (pintype "passive"))
      (node (ref "BLEND") (pin "P$6") (pinfunction "1_P$6") (pintype "passive"))
      (node (ref "C10") (pin "2") (pinfunction "2_2") (pintype "passive"))
      (node (ref "C11") (pin "2") (pinfunction "2_2") (pintype "passive"))
      (node (ref "C13") (pin "2") (pinfunction "2_2") (pintype "passive"))
      (node (ref "C35") (pin "+") (pinfunction "+_+") (pintype "passive"))
      (node (ref "DRIVE") (pin "P$2") (pinfunction "2_P$2") (pintype "passive"))
      (node (ref "DRIVE") (pin "P$3") (pinfunction "3_P$3") (pintype "passive"))
      (node (ref "LEVEL") (pin "P$1") (pinfunction "1_P$1") (pintype "passive"))
      (node (ref "R14") (pin "1") (pinfunction "1_1") (pintype "passive"))
      (node (ref "R2") (pin "2") (pinfunction "2_2") (pintype "passive"))
      (node (ref "R20") (pin "1") (pinfunction "1_1") (pintype "passive"))
      (node (ref "R33") (pin "1") (pinfunction "1_1") (pintype "passive"))
      (node (ref "R36") (pin "2") (pinfunction "2_2") (pintype "passive"))
      (node (ref "R4") (pin "1") (pinfunction "1_1") (pintype "passive"))
      (node (ref "R44") (pin "2") (pinfunction "2_2") (pintype "passive"))
      (node (ref "R45") (pin "1") (pinfunction "1_1") (pintype "passive"))
      (node (ref "R5") (pin "1") (pinfunction "1_1") (pintype "passive"))
      (node (ref "R6") (pin "2") (pinfunction "2_2") (pintype "passive"))
      (node (ref "SHAPE") (pin "P$2") (pinfunction "2_P$2") (pintype "passive"))
      (node (ref "SHAPE") (pin "P$3") (pinfunction "3_P$3") (pintype "passive"))
      (node (ref "U2") (pin "12") (pinfunction "IN+_12") (pintype "input"))
      (node (ref "U3") (pin "3") (pinfunction "IN+_3") (pintype "input"))
      (node (ref "U4") (pin "3") (pinfunction "IN+_3") (pintype "input"))
    )
  )
)
